# sensor.net
KiCad netlist of a schematic drawn in EAGLE
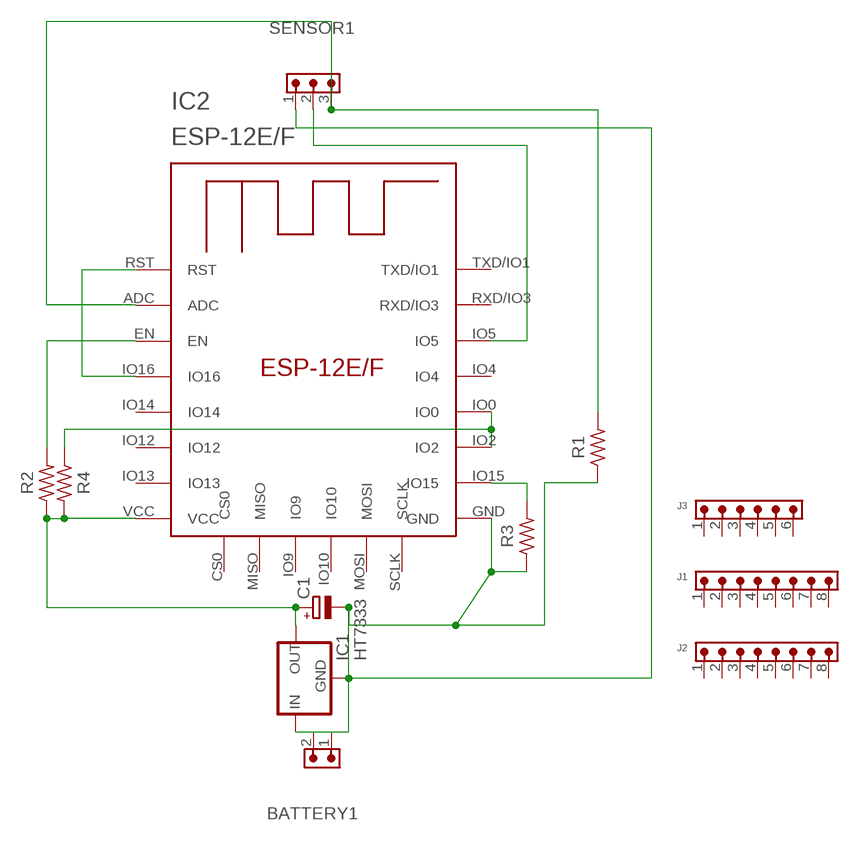
[diagram p0: schematic, sheet 1]

(export (version "E")
  (design (tool "Eeschema 10.0.6"))
  (components
    (comp (ref "BATTERY1")
      (value "6130XX11121_61300211121")
      (footprint "eagle-import:61300211121")
      (libsource (lib "eagle-import") (part "6130XX11121_61300211121"))
    )
    (comp (ref "C1")
      (value "CPOL-EUE2-5")
      (footprint "eagle-import:E2-5")
      (libsource (lib "eagle-import") (part "CPOL-EUE2-5"))
    )
    (comp (ref "IC1")
      (value "HT7333")
      (footprint "eagle-import:SOT-89")
      (libsource (lib "eagle-import") (part "HT7333"))
    )
    (comp (ref "IC2")
      (value "ESP-12E/F")
      (footprint "eagle-import:ESP-12E")
      (libsource (lib "eagle-import") (part "ESP-12E/F"))
    )
    (comp (ref "J1")
      (value "6200XX11121_62000811121")
      (footprint "eagle-import:62000811121")
      (libsource (lib "eagle-import") (part "6200XX11121_62000811121"))
    )
    (comp (ref "J2")
      (value "6200XX11121_62000811121")
      (footprint "eagle-import:62000811121")
      (libsource (lib "eagle-import") (part "6200XX11121_62000811121"))
    )
    (comp (ref "J3")
      (value "6200XX11121_62000611121")
      (footprint "eagle-import:62000611121")
      (libsource (lib "eagle-import") (part "6200XX11121_62000611121"))
    )
    (comp (ref "R1")
      (value "R-US_AXIAL-7.2MM-PITCH")
      (footprint "eagle-import:RESAD724W46L381D178B")
      (libsource (lib "eagle-import") (part "R-USAXIAL-7.2MM-PITCH_"))
    )
    (comp (ref "R2")
      (value "R-US_AXIAL-7.2MM-PITCH")
      (footprint "eagle-import:RESAD724W46L381D178B")
      (libsource (lib "eagle-import") (part "R-USAXIAL-7.2MM-PITCH_"))
    )
    (comp (ref "R3")
      (value "R-US_AXIAL-7.2MM-PITCH")
      (footprint "eagle-import:RESAD724W46L381D178B")
      (libsource (lib "eagle-import") (part "R-USAXIAL-7.2MM-PITCH_"))
    )
    (comp (ref "R4")
      (value "R-US_AXIAL-7.2MM-PITCH")
      (footprint "eagle-import:RESAD724W46L381D178B")
      (libsource (lib "eagle-import") (part "R-USAXIAL-7.2MM-PITCH_"))
    )
    (comp (ref "SENSOR1")
      (value "6130XX11121_61300311121")
      (footprint "eagle-import:61300311121")
      (libsource (lib "eagle-import") (part "6130XX11121_61300311121"))
    )
  )
  (nets
    (net (code "1") (name "Net-(BATTERY1-Pad1)") (class "Default")
      (node (ref "BATTERY1") (pin "1") (pinfunction "1_1") (pintype "passive"))
      (node (ref "IC1") (pin "3") (pinfunction "IN_3") (pintype "input"))
      (node (ref "IC1") (pin "4") (pinfunction "IN_4") (pintype "input"))
    )
    (net (code "2") (name "Net-(IC1-GND)") (class "Default")
      (node (ref "BATTERY1") (pin "2") (pinfunction "2_2") (pintype "passive"))
      (node (ref "C1") (pin "-") (pinfunction "-_-") (pintype "passive"))
      (node (ref "IC1") (pin "2") (pinfunction "GND_2") (pintype "input"))
      (node (ref "IC2") (pin "GND") (pinfunction "GND_GND") (pintype "power_in"))
      (node (ref "R1") (pin "1") (pinfunction "1_1") (pintype "passive"))
      (node (ref "R3") (pin "1") (pinfunction "1_1") (pintype "passive"))
      (node (ref "SENSOR1") (pin "1") (pinfunction "1_1") (pintype "passive"))
    )
    (net (code "3") (name "Net-(IC1-OUT)") (class "Default")
      (node (ref "C1") (pin "+") (pinfunction "+_+") (pintype "passive"))
      (node (ref "IC1") (pin "1") (pinfunction "OUT_1") (pintype "passive"))
      (node (ref "IC2") (pin "VCC") (pinfunction "VCC_VCC") (pintype "power_in"))
      (node (ref "R2") (pin "1") (pinfunction "1_1") (pintype "passive"))
      (node (ref "R4") (pin "2") (pinfunction "2_2") (pintype "passive"))
    )
    (net (code "4") (name "Net-(IC2-PadADC)") (class "Default")
      (node (ref "IC2") (pin "ADC") (pinfunction "ADC_ADC") (pintype "bidirectional"))
      (node (ref "R1") (pin "2") (pinfunction "2_2") (pintype "passive"))
      (node (ref "SENSOR1") (pin "3") (pinfunction "3_3") (pintype "passive"))
    )
    (net (code "5") (name "Net-(IC2-PadEN)") (class "Default")
      (node (ref "IC2") (pin "EN") (pinfunction "EN_EN") (pintype "bidirectional"))
      (node (ref "R2") (pin "2") (pinfunction "2_2") (pintype "passive"))
    )
    (net (code "6") (name "Net-(IC2-PadIO0)") (class "Default")
      (node (ref "IC2") (pin "IO0") (pinfunction "IO0_IO0") (pintype "bidirectional"))
      (node (ref "IC2") (pin "IO2") (pinfunction "IO2_IO2") (pintype "bidirectional"))
      (node (ref "R4") (pin "1") (pinfunction "1_1") (pintype "passive"))
    )
    (net (code "7") (name "Net-(IC2-PadIO5)") (class "Default")
      (node (ref "IC2") (pin "IO5") (pinfunction "IO5_IO5") (pintype "bidirectional"))
      (node (ref "SENSOR1") (pin "2") (pinfunction "2_2") (pintype "passive"))
    )
    (net (code "8") (name "Net-(IC2-PadIO15)") (class "Default")
      (node (ref "IC2") (pin "IO15") (pinfunction "IO15_IO15") (pintype "bidirectional"))
      (node (ref "R3") (pin "2") (pinfunction "2_2") (pintype "passive"))
    )
    (net (code "9") (name "Net-(IC2-PadIO16)") (class "Default")
      (node (ref "IC2") (pin "IO16") (pinfunction "IO16_IO16") (pintype "bidirectional"))
      (node (ref "IC2") (pin "RST") (pinfunction "RST_RST") (pintype "input"))
    )
    (net (code "10") (name "unconnected-(IC2-PadCS0)") (class "Default")
      (node (ref "IC2") (pin "CS0") (pinfunction "CS0_CS0") (pintype "bidirectional"))
    )
    (net (code "11") (name "unconnected-(IC2-PadIO4)") (class "Default")
      (node (ref "IC2") (pin "IO4") (pinfunction "IO4_IO4") (pintype "bidirectional"))
    )
    (net (code "12") (name "unconnected-(IC2-PadIO9)") (class "Default")
      (node (ref "IC2") (pin "IO9") (pinfunction "IO9_IO9") (pintype "bidirectional"))
    )
    (net (code "13") (name "unconnected-(IC2-PadIO10)") (class "Default")
      (node (ref "IC2") (pin "IO10") (pinfunction "IO10_IO10") (pintype "bidirectional"))
    )
    (net (code "14") (name "unconnected-(IC2-PadIO12)") (class "Default")
      (node (ref "IC2") (pin "IO12") (pinfunction "IO12_IO12") (pintype "bidirectional"))
    )
    (net (code "15") (name "unconnected-(IC2-PadIO13)") (class "Default")
      (node (ref "IC2") (pin "IO13") (pinfunction "IO13_IO13") (pintype "bidirectional"))
    )
    (net (code "16") (name "unconnected-(IC2-PadIO14)") (class "Default")
      (node (ref "IC2") (pin "IO14") (pinfunction "IO14_IO14") (pintype "bidirectional"))
    )
    (net (code "17") (name "unconnected-(IC2-PadMISO)") (class "Default")
      (node (ref "IC2") (pin "MISO") (pinfunction "MISO_MISO") (pintype "bidirectional"))
    )
    (net (code "18") (name "unconnected-(IC2-PadMOSI)") (class "Default")
      (node (ref "IC2") (pin "MOSI") (pinfunction "MOSI_MOSI") (pintype "bidirectional"))
    )
    (net (code "19") (name "unconnected-(IC2-PadRXD{slash}IO3)") (class "Default")
      (node (ref "IC2") (pin "RXD/IO3") (pinfunction "RXD/IO3_RXD/IO3") (pintype "bidirectional"))
    )
    (net (code "20") (name "unconnected-(IC2-PadSCLK)") (class "Default")
      (node (ref "IC2") (pin "SCLK") (pinfunction "SCLK_SCLK") (pintype "bidirectional"))
    )
    (net (code "21") (name "unconnected-(IC2-PadTXD{slash}IO1)") (class "Default")
      (node (ref "IC2") (pin "TXD/IO1") (pinfunction "TXD/IO1_TXD/IO1") (pintype "bidirectional"))
    )
    (net (code "22") (name "unconnected-(J1-Pad1)") (class "Default")
      (node (ref "J1") (pin "1") (pinfunction "1_1") (pintype "passive"))
    )
    (net (code "23") (name "unconnected-(J1-Pad2)") (class "Default")
      (node (ref "J1") (pin "2") (pinfunction "2_2") (pintype "passive"))
    )
    (net (code "24") (name "unconnected-(J1-Pad3)") (class "Default")
      (node (ref "J1") (pin "3") (pinfunction "3_3") (pintype "passive"))
    )
    (net (code "25") (name "unconnected-(J1-Pad4)") (class "Default")
      (node (ref "J1") (pin "4") (pinfunction "4_4") (pintype "passive"))
    )
    (net (code "26") (name "unconnected-(J1-Pad5)") (class "Default")
      (node (ref "J1") (pin "5") (pinfunction "5_5") (pintype "passive"))
    )
    (net (code "27") (name "unconnected-(J1-Pad6)") (class "Default")
      (node (ref "J1") (pin "6") (pinfunction "6_6") (pintype "passive"))
    )
    (net (code "28") (name "unconnected-(J1-Pad7)") (class "Default")
      (node (ref "J1") (pin "7") (pinfunction "7_7") (pintype "passive"))
    )
    (net (code "29") (name "unconnected-(J1-Pad8)") (class "Default")
      (node (ref "J1") (pin "8") (pinfunction "8_8") (pintype "passive"))
    )
    (net (code "30") (name "unconnected-(J2-Pad1)") (class "Default")
      (node (ref "J2") (pin "1") (pinfunction "1_1") (pintype "passive"))
    )
    (net (code "31") (name "unconnected-(J2-Pad2)") (class "Default")
      (node (ref "J2") (pin "2") (pinfunction "2_2") (pintype "passive"))
    )
    (net (code "32") (name "unconnected-(J2-Pad3)") (class "Default")
      (node (ref "J2") (pin "3") (pinfunction "3_3") (pintype "passive"))
    )
    (net (code "33") (name "unconnected-(J2-Pad4)") (class "Default")
      (node (ref "J2") (pin "4") (pinfunction "4_4") (pintype "passive"))
    )
    (net (code "34") (name "unconnected-(J2-Pad5)") (class "Default")
      (node (ref "J2") (pin "5") (pinfunction "5_5") (pintype "passive"))
    )
    (net (code "35") (name "unconnected-(J2-Pad6)") (class "Default")
      (node (ref "J2") (pin "6") (pinfunction "6_6") (pintype "passive"))
    )
    (net (code "36") (name "unconnected-(J2-Pad7)") (class "Default")
      (node (ref "J2") (pin "7") (pinfunction "7_7") (pintype "passive"))
    )
    (net (code "37") (name "unconnected-(J2-Pad8)") (class "Default")
      (node (ref "J2") (pin "8") (pinfunction "8_8") (pintype "passive"))
    )
    (net (code "38") (name "unconnected-(J3-Pad1)") (class "Default")
      (node (ref "J3") (pin "1") (pinfunction "1_1") (pintype "passive"))
    )
    (net (code "39") (name "unconnected-(J3-Pad2)") (class "Default")
      (node (ref "J3") (pin "2") (pinfunction "2_2") (pintype "passive"))
    )
    (net (code "40") (name "unconnected-(J3-Pad3)") (class "Default")
      (node (ref "J3") (pin "3") (pinfunction "3_3") (pintype "passive"))
    )
    (net (code "41") (name "unconnected-(J3-Pad4)") (class "Default")
      (node (ref "J3") (pin "4") (pinfunction "4_4") (pintype "passive"))
    )
    (net (code "42") (name "unconnected-(J3-Pad5)") (class "Default")
      (node (ref "J3") (pin "5") (pinfunction "5_5") (pintype "passive"))
    )
    (net (code "43") (name "unconnected-(J3-Pad6)") (class "Default")
      (node (ref "J3") (pin "6") (pinfunction "6_6") (pintype "passive"))
    )
  )
)
